# VHF-Superregen.net
KiCad netlist of a schematic drawn in EAGLE
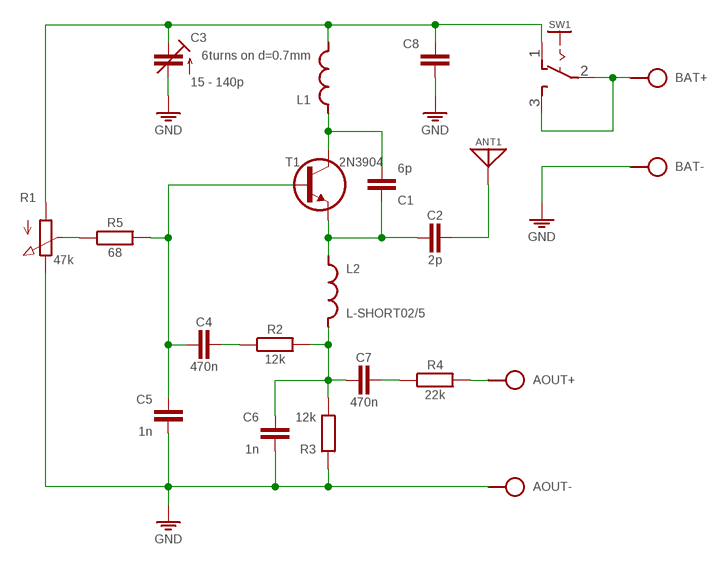
[diagram p0: schematic, sheet 1]

(export (version "E")
  (design (tool "Eeschema 10.0.6"))
  (components
    (comp (ref "ANT1")
      (value "ANT")
      (footprint "eagle-import:SPAD")
      (libsource (lib "eagle-import") (part "ANT"))
    )
    (comp (ref "AOUT+")
      (value "SPAD")
      (footprint "eagle-import:SPAD")
      (libsource (lib "eagle-import") (part "SPAD"))
    )
    (comp (ref "AOUT-")
      (value "SPAD")
      (footprint "eagle-import:SPAD")
      (libsource (lib "eagle-import") (part "SPAD"))
    )
    (comp (ref "BAT+")
      (value "SPAD")
      (footprint "eagle-import:SPAD")
      (libsource (lib "eagle-import") (part "SPAD"))
    )
    (comp (ref "BAT-")
      (value "SPAD")
      (footprint "eagle-import:SPAD")
      (libsource (lib "eagle-import") (part "SPAD"))
    )
    (comp (ref "C1")
      (value "6p")
      (footprint "eagle-import:C050-020X036")
      (libsource (lib "eagle-import") (part "C050-020X036"))
    )
    (comp (ref "C2")
      (value "2p")
      (footprint "eagle-import:C025-015X024")
      (libsource (lib "eagle-import") (part "C025-015X024"))
    )
    (comp (ref "C3")
      (value "15 - 140p")
      (footprint "eagle-import:TRIM-2222-808")
      (libsource (lib "eagle-import") (part "C-TR-PH201272222-808-2PINB"))
    )
    (comp (ref "C4")
      (value "470n")
      (footprint "eagle-import:C050-020X036")
      (libsource (lib "eagle-import") (part "C050-020X036"))
    )
    (comp (ref "C5")
      (value "1n")
      (footprint "eagle-import:C025-020X036")
      (libsource (lib "eagle-import") (part "C025-020X036"))
    )
    (comp (ref "C6")
      (value "1n")
      (footprint "eagle-import:C050-020X036")
      (libsource (lib "eagle-import") (part "C050-020X036"))
    )
    (comp (ref "C7")
      (value "470n")
      (footprint "eagle-import:C050-020X036")
      (libsource (lib "eagle-import") (part "C050-020X036"))
    )
    (comp (ref "C8")
      (value "C050-025X075")
      (footprint "eagle-import:C050-025X075")
      (libsource (lib "eagle-import") (part "C050-025X075"))
    )
    (comp (ref "L1")
      (value "6turns on d=0.7mm")
      (footprint "eagle-import:L-04-5_5V")
      (libsource (lib "eagle-import") (part "L-SHORT04-5/5V"))
    )
    (comp (ref "L2")
      (value "L-SHORT02/5")
      (footprint "eagle-import:L-02_5V")
      (libsource (lib "eagle-import") (part "r_L-SHORT02/5"))
    )
    (comp (ref "R1")
      (value "47k")
      (footprint "eagle-import:POT")
      (libsource (lib "eagle-import") (part "POT"))
    )
    (comp (ref "R2")
      (value "12k")
      (footprint "eagle-import:0202_7")
      (libsource (lib "eagle-import") (part "R-H0202/7"))
    )
    (comp (ref "R3")
      (value "12k")
      (footprint "eagle-import:0202_7")
      (libsource (lib "eagle-import") (part "R0202/7"))
    )
    (comp (ref "R4")
      (value "22k")
      (footprint "eagle-import:0202_7")
      (libsource (lib "eagle-import") (part "R-H0202/7"))
    )
    (comp (ref "R5")
      (value "68")
      (footprint "eagle-import:0202_7")
      (libsource (lib "eagle-import") (part "R-H0202/7"))
    )
    (comp (ref "SW1")
      (value "SL-SW-1P-2T-H")
      (footprint "eagle-import:SLSW-1P2T-H")
      (libsource (lib "eagle-import") (part "SL-SW-1P-2T-H"))
    )
    (comp (ref "T1")
      (value "2N3904")
      (footprint "eagle-import:TO92")
      (libsource (lib "eagle-import") (part "2N3904"))
    )
  )
  (nets
    (net (code "1") (name "GND") (class "Default")
      (node (ref "AOUT-") (pin "1") (pinfunction "P$1_1") (pintype "bidirectional"))
      (node (ref "BAT-") (pin "1") (pinfunction "P$1_1") (pintype "bidirectional"))
      (node (ref "C3") (pin "2") (pinfunction "A_2") (pintype "passive"))
      (node (ref "C5") (pin "2") (pinfunction "2_2") (pintype "passive"))
      (node (ref "C6") (pin "2") (pinfunction "2_2") (pintype "passive"))
      (node (ref "C8") (pin "2") (pinfunction "2_2") (pintype "passive"))
      (node (ref "R1") (pin "3") (pinfunction "E_3") (pintype "passive"))
      (node (ref "R3") (pin "2") (pinfunction "2_2") (pintype "passive"))
    )
    (net (code "2") (name "Net-(ANT1-Pad1)") (class "Default")
      (node (ref "ANT1") (pin "1") (pinfunction "1_1") (pintype "output"))
      (node (ref "C2") (pin "1") (pinfunction "1_1") (pintype "passive"))
    )
    (net (code "3") (name "Net-(AOUT+-P$1)") (class "Default")
      (node (ref "AOUT+") (pin "1") (pinfunction "P$1_1") (pintype "bidirectional"))
      (node (ref "R4") (pin "2") (pinfunction "2_2") (pintype "passive"))
    )
    (net (code "4") (name "Net-(BAT+-P$1)") (class "Default")
      (node (ref "BAT+") (pin "1") (pinfunction "P$1_1") (pintype "bidirectional"))
      (node (ref "SW1") (pin "2") (pinfunction "P_2") (pintype "passive"))
      (node (ref "SW1") (pin "3") (pinfunction "S_3") (pintype "passive"))
    )
    (net (code "5") (name "Net-(C3-E)") (class "Default")
      (node (ref "C3") (pin "3") (pinfunction "E_3") (pintype "passive"))
      (node (ref "C8") (pin "1") (pinfunction "1_1") (pintype "passive"))
      (node (ref "L1") (pin "1") (pinfunction "1_1") (pintype "passive"))
      (node (ref "R1") (pin "1") (pinfunction "A_1") (pintype "passive"))
      (node (ref "SW1") (pin "1") (pinfunction "O_1") (pintype "passive"))
    )
    (net (code "6") (name "Net-(C4-Pad1)") (class "Default")
      (node (ref "C4") (pin "1") (pinfunction "1_1") (pintype "passive"))
      (node (ref "R2") (pin "1") (pinfunction "1_1") (pintype "passive"))
    )
    (net (code "7") (name "Net-(C6-Pad1)") (class "Default")
      (node (ref "C6") (pin "1") (pinfunction "1_1") (pintype "passive"))
      (node (ref "C7") (pin "2") (pinfunction "2_2") (pintype "passive"))
      (node (ref "L2") (pin "2") (pinfunction "2_2") (pintype "passive"))
      (node (ref "R2") (pin "2") (pinfunction "2_2") (pintype "passive"))
      (node (ref "R3") (pin "1") (pinfunction "1_1") (pintype "passive"))
    )
    (net (code "8") (name "Net-(C7-Pad1)") (class "Default")
      (node (ref "C7") (pin "1") (pinfunction "1_1") (pintype "passive"))
      (node (ref "R4") (pin "1") (pinfunction "1_1") (pintype "passive"))
    )
    (net (code "9") (name "Net-(R1-S)") (class "Default")
      (node (ref "R1") (pin "2") (pinfunction "S_2") (pintype "passive"))
      (node (ref "R5") (pin "1") (pinfunction "1_1") (pintype "passive"))
    )
    (net (code "10") (name "Net-(T1-B)") (class "Default")
      (node (ref "C4") (pin "2") (pinfunction "2_2") (pintype "passive"))
      (node (ref "C5") (pin "1") (pinfunction "1_1") (pintype "passive"))
      (node (ref "R5") (pin "2") (pinfunction "2_2") (pintype "passive"))
      (node (ref "T1") (pin "2") (pinfunction "B_2") (pintype "passive"))
    )
    (net (code "11") (name "Net-(T1-C)") (class "Default")
      (node (ref "C1") (pin "2") (pinfunction "2_2") (pintype "passive"))
      (node (ref "L1") (pin "2") (pinfunction "2_2") (pintype "passive"))
      (node (ref "T1") (pin "3") (pinfunction "C_3") (pintype "passive"))
    )
    (net (code "12") (name "Net-(T1-E)") (class "Default")
      (node (ref "C1") (pin "1") (pinfunction "1_1") (pintype "passive"))
      (node (ref "C2") (pin "2") (pinfunction "2_2") (pintype "passive"))
      (node (ref "L2") (pin "1") (pinfunction "1_1") (pintype "passive"))
      (node (ref "T1") (pin "1") (pinfunction "E_1") (pintype "passive"))
    )
  )
)
